# MCU.net
KiCad netlist of a schematic drawn in Altium Designer
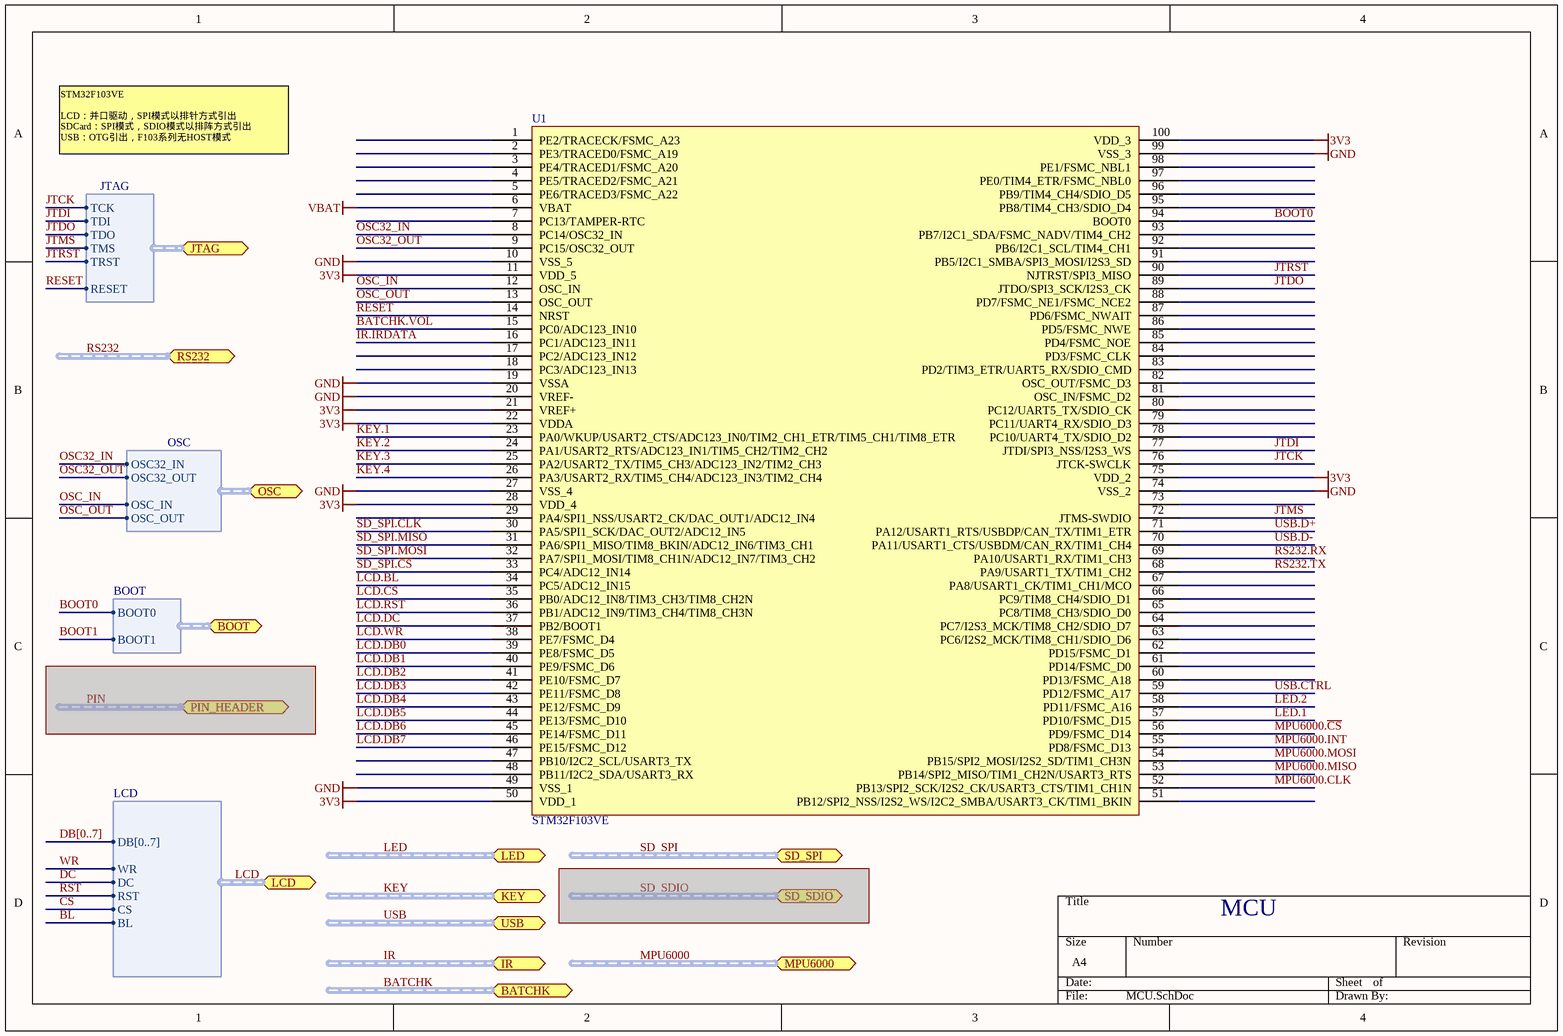
[diagram p0: MCU.SchDoc]

(export (version "E")
  (design (tool "Eeschema 10.0.6"))
  (components
    (comp (ref "U1")
      (value "STM32F103VE")
      (footprint "LQFP100_M")
      (libsource (lib "STM32F103VE") (part "STM32F103VE"))
    )
  )
  (nets
    (net (code "15") (name "/BATCHK.VOL") (class "Default")
      (node (ref "U1") (pin "15") (pinfunction "PC0/ADC123_IN10_15") (pintype "passive"))
    )
    (net (code "17") (name "/BOOT0") (class "Default")
      (node (ref "U1") (pin "94") (pinfunction "BOOT0_94") (pintype "passive"))
    )
    (net (code "21") (name "/IR.IRDATA") (class "Default")
      (node (ref "U1") (pin "16") (pinfunction "PC1/ADC123_IN11_16") (pintype "passive"))
    )
    (net (code "22") (name "/JTCK") (class "Default")
      (node (ref "U1") (pin "76") (pinfunction "JTCK-SWCLK_76") (pintype "passive"))
    )
    (net (code "23") (name "/JTDI") (class "Default")
      (node (ref "U1") (pin "77") (pinfunction "JTDI/SPI3_NSS/I2S3_WS_77") (pintype "passive"))
    )
    (net (code "24") (name "/JTDO") (class "Default")
      (node (ref "U1") (pin "89") (pinfunction "JTDO/SPI3_SCK/I2S3_CK_89") (pintype "passive"))
    )
    (net (code "25") (name "/JTMS") (class "Default")
      (node (ref "U1") (pin "72") (pinfunction "JTMS-SWDIO_72") (pintype "passive"))
    )
    (net (code "26") (name "/JTRST") (class "Default")
      (node (ref "U1") (pin "90") (pinfunction "NJTRST/SPI3_MISO_90") (pintype "passive"))
    )
    (net (code "27") (name "/KEY.1") (class "Default")
      (node (ref "U1") (pin "23") (pinfunction "PA0/WKUP/USART2_CTS/ADC123_IN0/TIM2_CH1_ETR/TIM5_CH1/TIM8_ETR_23") (pintype "passive"))
    )
    (net (code "28") (name "/KEY.2") (class "Default")
      (node (ref "U1") (pin "24") (pinfunction "PA1/USART2_RTS/ADC123_IN1/TIM5_CH2/TIM2_CH2_24") (pintype "passive"))
    )
    (net (code "29") (name "/KEY.3") (class "Default")
      (node (ref "U1") (pin "25") (pinfunction "PA2/USART2_TX/TIM5_CH3/ADC123_IN2/TIM2_CH3_25") (pintype "passive"))
    )
    (net (code "30") (name "/KEY.4") (class "Default")
      (node (ref "U1") (pin "26") (pinfunction "PA3/USART2_RX/TIM5_CH4/ADC123_IN3/TIM2_CH4_26") (pintype "passive"))
    )
    (net (code "31") (name "/LCD.BL") (class "Default")
      (node (ref "U1") (pin "34") (pinfunction "PC5/ADC12_IN15_34") (pintype "passive"))
    )
    (net (code "32") (name "/LCD.CS") (class "Default")
      (node (ref "U1") (pin "35") (pinfunction "PB0/ADC12_IN8/TIM3_CH3/TIM8_CH2N_35") (pintype "passive"))
    )
    (net (code "33") (name "/LCD.DB0") (class "Default")
      (node (ref "U1") (pin "39") (pinfunction "PE8/FSMC_D5_39") (pintype "passive"))
    )
    (net (code "34") (name "/LCD.DB1") (class "Default")
      (node (ref "U1") (pin "40") (pinfunction "PE9/FSMC_D6_40") (pintype "passive"))
    )
    (net (code "35") (name "/LCD.DB2") (class "Default")
      (node (ref "U1") (pin "41") (pinfunction "PE10/FSMC_D7_41") (pintype "passive"))
    )
    (net (code "36") (name "/LCD.DB3") (class "Default")
      (node (ref "U1") (pin "42") (pinfunction "PE11/FSMC_D8_42") (pintype "passive"))
    )
    (net (code "37") (name "/LCD.DB4") (class "Default")
      (node (ref "U1") (pin "43") (pinfunction "PE12/FSMC_D9_43") (pintype "passive"))
    )
    (net (code "38") (name "/LCD.DB5") (class "Default")
      (node (ref "U1") (pin "44") (pinfunction "PE13/FSMC_D10_44") (pintype "passive"))
    )
    (net (code "39") (name "/LCD.DB6") (class "Default")
      (node (ref "U1") (pin "45") (pinfunction "PE14/FSMC_D11_45") (pintype "passive"))
    )
    (net (code "40") (name "/LCD.DB7") (class "Default")
      (node (ref "U1") (pin "46") (pinfunction "PE15/FSMC_D12_46") (pintype "passive"))
    )
    (net (code "41") (name "/LCD.DC") (class "Default")
      (node (ref "U1") (pin "37") (pinfunction "PB2/BOOT1_37") (pintype "passive"))
    )
    (net (code "42") (name "/LCD.RST") (class "Default")
      (node (ref "U1") (pin "36") (pinfunction "PB1/ADC12_IN9/TIM3_CH4/TIM8_CH3N_36") (pintype "passive"))
    )
    (net (code "43") (name "/LCD.WR") (class "Default")
      (node (ref "U1") (pin "38") (pinfunction "PE7/FSMC_D4_38") (pintype "passive"))
    )
    (net (code "44") (name "/LED.1") (class "Default")
      (node (ref "U1") (pin "57") (pinfunction "PD10/FSMC_D15_57") (pintype "passive"))
    )
    (net (code "45") (name "/LED.2") (class "Default")
      (node (ref "U1") (pin "58") (pinfunction "PD11/FSMC_A16_58") (pintype "passive"))
    )
    (net (code "46") (name "/MPU6000.CLK") (class "Default")
      (node (ref "U1") (pin "52") (pinfunction "PB13/SPI2_SCK/I2S2_CK/USART3_CTS/TIM1_CH1N_52") (pintype "passive"))
    )
    (net (code "47") (name "/MPU6000.INT") (class "Default")
      (node (ref "U1") (pin "55") (pinfunction "PD8/FSMC_D13_55") (pintype "passive"))
    )
    (net (code "48") (name "/MPU6000.MISO") (class "Default")
      (node (ref "U1") (pin "53") (pinfunction "PB14/SPI2_MISO/TIM1_CH2N/USART3_RTS_53") (pintype "passive"))
    )
    (net (code "49") (name "/MPU6000.MOSI") (class "Default")
      (node (ref "U1") (pin "54") (pinfunction "PB15/SPI2_MOSI/I2S2_SD/TIM1_CH3N_54") (pintype "passive"))
    )
    (net (code "50") (name "/MPU6000.~{CS}") (class "Default")
      (node (ref "U1") (pin "56") (pinfunction "PD9/FSMC_D14_56") (pintype "passive"))
    )
    (net (code "51") (name "/OSC32_IN") (class "Default")
      (node (ref "U1") (pin "8") (pinfunction "PC14/OSC32_IN_8") (pintype "passive"))
    )
    (net (code "52") (name "/OSC32_OUT") (class "Default")
      (node (ref "U1") (pin "9") (pinfunction "PC15/OSC32_OUT_9") (pintype "passive"))
    )
    (net (code "53") (name "/OSC_IN") (class "Default")
      (node (ref "U1") (pin "12") (pinfunction "OSC_IN_12") (pintype "passive"))
    )
    (net (code "54") (name "/OSC_OUT") (class "Default")
      (node (ref "U1") (pin "13") (pinfunction "OSC_OUT_13") (pintype "passive"))
    )
    (net (code "55") (name "/RESET") (class "Default")
      (node (ref "U1") (pin "14") (pinfunction "NRST_14") (pintype "passive"))
    )
    (net (code "56") (name "/RS232.RX") (class "Default")
      (node (ref "U1") (pin "69") (pinfunction "PA10/USART1_RX/TIM1_CH3_69") (pintype "passive"))
    )
    (net (code "57") (name "/RS232.TX") (class "Default")
      (node (ref "U1") (pin "68") (pinfunction "PA9/USART1_TX/TIM1_CH2_68") (pintype "passive"))
    )
    (net (code "59") (name "/SD_SPI.CLK") (class "Default")
      (node (ref "U1") (pin "30") (pinfunction "PA5/SPI1_SCK/DAC_OUT2/ADC12_IN5_30") (pintype "passive"))
    )
    (net (code "60") (name "/SD_SPI.MISO") (class "Default")
      (node (ref "U1") (pin "31") (pinfunction "PA6/SPI1_MISO/TIM8_BKIN/ADC12_IN6/TIM3_CH1_31") (pintype "passive"))
    )
    (net (code "61") (name "/SD_SPI.MOSI") (class "Default")
      (node (ref "U1") (pin "32") (pinfunction "PA7/SPI1_MOSI/TIM8_CH1N/ADC12_IN7/TIM3_CH2_32") (pintype "passive"))
    )
    (net (code "62") (name "/SD_SPI.~{CS}") (class "Default")
      (node (ref "U1") (pin "33") (pinfunction "PC4/ADC12_IN14_33") (pintype "passive"))
    )
    (net (code "63") (name "/USB.CTRL") (class "Default")
      (node (ref "U1") (pin "59") (pinfunction "PD12/FSMC_A17_59") (pintype "passive"))
    )
    (net (code "64") (name "/USB.D+") (class "Default")
      (node (ref "U1") (pin "71") (pinfunction "PA12/USART1_RTS/USBDP/CAN_TX/TIM1_ETR_71") (pintype "passive"))
    )
    (net (code "65") (name "/USB.D-") (class "Default")
      (node (ref "U1") (pin "70") (pinfunction "PA11/USART1_CTS/USBDM/CAN_RX/TIM1_CH4_70") (pintype "passive"))
    )
    (net (code "82") (name "3V3") (class "Default")
      (node (ref "U1") (pin "100") (pinfunction "VDD_3_100") (pintype "passive"))
      (node (ref "U1") (pin "11") (pinfunction "VDD_5_11") (pintype "passive"))
      (node (ref "U1") (pin "21") (pinfunction "VREF+_21") (pintype "passive"))
      (node (ref "U1") (pin "22") (pinfunction "VDDA_22") (pintype "passive"))
      (node (ref "U1") (pin "28") (pinfunction "VDD_4_28") (pintype "passive"))
      (node (ref "U1") (pin "50") (pinfunction "VDD_1_50") (pintype "passive"))
      (node (ref "U1") (pin "75") (pinfunction "VDD_2_75") (pintype "passive"))
    )
    (net (code "83") (name "GND") (class "Default")
      (node (ref "U1") (pin "10") (pinfunction "VSS_5_10") (pintype "passive"))
      (node (ref "U1") (pin "19") (pinfunction "VSSA_19") (pintype "passive"))
      (node (ref "U1") (pin "20") (pinfunction "VREF-_20") (pintype "passive"))
      (node (ref "U1") (pin "27") (pinfunction "VSS_4_27") (pintype "passive"))
      (node (ref "U1") (pin "49") (pinfunction "VSS_1_49") (pintype "passive"))
      (node (ref "U1") (pin "74") (pinfunction "VSS_2_74") (pintype "passive"))
      (node (ref "U1") (pin "99") (pinfunction "VSS_3_99") (pintype "passive"))
    )
    (net (code "84") (name "VBAT") (class "Default")
      (node (ref "U1") (pin "6") (pinfunction "VBAT_6") (pintype "passive"))
    )
    (net (code "85") (name "unconnected-(U1-OSC_IN{slash}FSMC_D2-Pad81)") (class "Default")
      (node (ref "U1") (pin "81") (pinfunction "OSC_IN/FSMC_D2_81") (pintype "passive"))
    )
    (net (code "86") (name "unconnected-(U1-OSC_OUT{slash}FSMC_D3-Pad82)") (class "Default")
      (node (ref "U1") (pin "82") (pinfunction "OSC_OUT/FSMC_D3_82") (pintype "passive"))
    )
    (net (code "87") (name "unconnected-(U1-PA4{slash}SPI1_NSS{slash}USART2_CK{slash}DAC_OUT1{slash}ADC12_IN4-Pad29)") (class "Default")
      (node (ref "U1") (pin "29") (pinfunction "PA4/SPI1_NSS/USART2_CK/DAC_OUT1/ADC12_IN4_29") (pintype "passive"))
    )
    (net (code "88") (name "unconnected-(U1-PA8{slash}USART1_CK{slash}TIM1_CH1{slash}MCO-Pad67)") (class "Default")
      (node (ref "U1") (pin "67") (pinfunction "PA8/USART1_CK/TIM1_CH1/MCO_67") (pintype "passive"))
    )
    (net (code "89") (name "unconnected-(U1-PB5{slash}I2C1_SMBA{slash}SPI3_MOSI{slash}I2S3_SD-Pad91)") (class "Default")
      (node (ref "U1") (pin "91") (pinfunction "PB5/I2C1_SMBA/SPI3_MOSI/I2S3_SD_91") (pintype "passive"))
    )
    (net (code "90") (name "unconnected-(U1-PB6{slash}I2C1_SCL{slash}TIM4_CH1-Pad92)") (class "Default")
      (node (ref "U1") (pin "92") (pinfunction "PB6/I2C1_SCL/TIM4_CH1_92") (pintype "passive"))
    )
    (net (code "91") (name "unconnected-(U1-PB7{slash}I2C1_SDA{slash}FSMC_NADV{slash}TIM4_CH2-Pad93)") (class "Default")
      (node (ref "U1") (pin "93") (pinfunction "PB7/I2C1_SDA/FSMC_NADV/TIM4_CH2_93") (pintype "passive"))
    )
    (net (code "92") (name "unconnected-(U1-PB8{slash}TIM4_CH3{slash}SDIO_D4-Pad95)") (class "Default")
      (node (ref "U1") (pin "95") (pinfunction "PB8/TIM4_CH3/SDIO_D4_95") (pintype "passive"))
    )
    (net (code "93") (name "unconnected-(U1-PB9{slash}TIM4_CH4{slash}SDIO_D5-Pad96)") (class "Default")
      (node (ref "U1") (pin "96") (pinfunction "PB9/TIM4_CH4/SDIO_D5_96") (pintype "passive"))
    )
    (net (code "94") (name "unconnected-(U1-PB10{slash}I2C2_SCL{slash}USART3_TX-Pad47)") (class "Default")
      (node (ref "U1") (pin "47") (pinfunction "PB10/I2C2_SCL/USART3_TX_47") (pintype "passive"))
    )
    (net (code "95") (name "unconnected-(U1-PB11{slash}I2C2_SDA{slash}USART3_RX-Pad48)") (class "Default")
      (node (ref "U1") (pin "48") (pinfunction "PB11/I2C2_SDA/USART3_RX_48") (pintype "passive"))
    )
    (net (code "96") (name "unconnected-(U1-PB12{slash}SPI2_NSS{slash}I2S2_WS{slash}I2C2_SMBA{slash}USART3_CK{slash}TIM1_BKIN-Pad51)") (class "Default")
      (node (ref "U1") (pin "51") (pinfunction "PB12/SPI2_NSS/I2S2_WS/I2C2_SMBA/USART3_CK/TIM1_BKIN_51") (pintype "passive"))
    )
    (net (code "97") (name "unconnected-(U1-PC2{slash}ADC123_IN12-Pad17)") (class "Default")
      (node (ref "U1") (pin "17") (pinfunction "PC2/ADC123_IN12_17") (pintype "passive"))
    )
    (net (code "98") (name "unconnected-(U1-PC3{slash}ADC123_IN13-Pad18)") (class "Default")
      (node (ref "U1") (pin "18") (pinfunction "PC3/ADC123_IN13_18") (pintype "passive"))
    )
    (net (code "99") (name "unconnected-(U1-PC6{slash}I2S2_MCK{slash}TIM8_CH1{slash}SDIO_D6-Pad63)") (class "Default")
      (node (ref "U1") (pin "63") (pinfunction "PC6/I2S2_MCK/TIM8_CH1/SDIO_D6_63") (pintype "passive"))
    )
    (net (code "100") (name "unconnected-(U1-PC7{slash}I2S3_MCK{slash}TIM8_CH2{slash}SDIO_D7-Pad64)") (class "Default")
      (node (ref "U1") (pin "64") (pinfunction "PC7/I2S3_MCK/TIM8_CH2/SDIO_D7_64") (pintype "passive"))
    )
    (net (code "101") (name "unconnected-(U1-PC8{slash}TIM8_CH3{slash}SDIO_D0-Pad65)") (class "Default")
      (node (ref "U1") (pin "65") (pinfunction "PC8/TIM8_CH3/SDIO_D0_65") (pintype "passive"))
    )
    (net (code "102") (name "unconnected-(U1-PC9{slash}TIM8_CH4{slash}SDIO_D1-Pad66)") (class "Default")
      (node (ref "U1") (pin "66") (pinfunction "PC9/TIM8_CH4/SDIO_D1_66") (pintype "passive"))
    )
    (net (code "103") (name "unconnected-(U1-PC10{slash}UART4_TX{slash}SDIO_D2-Pad78)") (class "Default")
      (node (ref "U1") (pin "78") (pinfunction "PC10/UART4_TX/SDIO_D2_78") (pintype "passive"))
    )
    (net (code "104") (name "unconnected-(U1-PC11{slash}UART4_RX{slash}SDIO_D3-Pad79)") (class "Default")
      (node (ref "U1") (pin "79") (pinfunction "PC11/UART4_RX/SDIO_D3_79") (pintype "passive"))
    )
    (net (code "105") (name "unconnected-(U1-PC12{slash}UART5_TX{slash}SDIO_CK-Pad80)") (class "Default")
      (node (ref "U1") (pin "80") (pinfunction "PC12/UART5_TX/SDIO_CK_80") (pintype "passive"))
    )
    (net (code "106") (name "unconnected-(U1-PC13{slash}TAMPER-RTC-Pad7)") (class "Default")
      (node (ref "U1") (pin "7") (pinfunction "PC13/TAMPER-RTC_7") (pintype "passive"))
    )
    (net (code "107") (name "unconnected-(U1-PD2{slash}TIM3_ETR{slash}UART5_RX{slash}SDIO_CMD-Pad83)") (class "Default")
      (node (ref "U1") (pin "83") (pinfunction "PD2/TIM3_ETR/UART5_RX/SDIO_CMD_83") (pintype "passive"))
    )
    (net (code "108") (name "unconnected-(U1-PD3{slash}FSMC_CLK-Pad84)") (class "Default")
      (node (ref "U1") (pin "84") (pinfunction "PD3/FSMC_CLK_84") (pintype "passive"))
    )
    (net (code "109") (name "unconnected-(U1-PD4{slash}FSMC_NOE-Pad85)") (class "Default")
      (node (ref "U1") (pin "85") (pinfunction "PD4/FSMC_NOE_85") (pintype "passive"))
    )
    (net (code "110") (name "unconnected-(U1-PD5{slash}FSMC_NWE-Pad86)") (class "Default")
      (node (ref "U1") (pin "86") (pinfunction "PD5/FSMC_NWE_86") (pintype "passive"))
    )
    (net (code "111") (name "unconnected-(U1-PD6{slash}FSMC_NWAIT-Pad87)") (class "Default")
      (node (ref "U1") (pin "87") (pinfunction "PD6/FSMC_NWAIT_87") (pintype "passive"))
    )
    (net (code "112") (name "unconnected-(U1-PD7{slash}FSMC_NE1{slash}FSMC_NCE2-Pad88)") (class "Default")
      (node (ref "U1") (pin "88") (pinfunction "PD7/FSMC_NE1/FSMC_NCE2_88") (pintype "passive"))
    )
    (net (code "113") (name "unconnected-(U1-PD13{slash}FSMC_A18-Pad60)") (class "Default")
      (node (ref "U1") (pin "60") (pinfunction "PD13/FSMC_A18_60") (pintype "passive"))
    )
    (net (code "114") (name "unconnected-(U1-PD14{slash}FSMC_D0-Pad61)") (class "Default")
      (node (ref "U1") (pin "61") (pinfunction "PD14/FSMC_D0_61") (pintype "passive"))
    )
    (net (code "115") (name "unconnected-(U1-PD15{slash}FSMC_D1-Pad62)") (class "Default")
      (node (ref "U1") (pin "62") (pinfunction "PD15/FSMC_D1_62") (pintype "passive"))
    )
    (net (code "116") (name "unconnected-(U1-PE0{slash}TIM4_ETR{slash}FSMC_NBL0-Pad97)") (class "Default")
      (node (ref "U1") (pin "97") (pinfunction "PE0/TIM4_ETR/FSMC_NBL0_97") (pintype "passive"))
    )
    (net (code "117") (name "unconnected-(U1-PE1{slash}FSMC_NBL1-Pad98)") (class "Default")
      (node (ref "U1") (pin "98") (pinfunction "PE1/FSMC_NBL1_98") (pintype "passive"))
    )
    (net (code "118") (name "unconnected-(U1-PE2{slash}TRACECK{slash}FSMC_A23-Pad1)") (class "Default")
      (node (ref "U1") (pin "1") (pinfunction "PE2/TRACECK/FSMC_A23_1") (pintype "passive"))
    )
    (net (code "119") (name "unconnected-(U1-PE3{slash}TRACED0{slash}FSMC_A19-Pad2)") (class "Default")
      (node (ref "U1") (pin "2") (pinfunction "PE3/TRACED0/FSMC_A19_2") (pintype "passive"))
    )
    (net (code "120") (name "unconnected-(U1-PE4{slash}TRACED1{slash}FSMC_A20-Pad3)") (class "Default")
      (node (ref "U1") (pin "3") (pinfunction "PE4/TRACED1/FSMC_A20_3") (pintype "passive"))
    )
    (net (code "121") (name "unconnected-(U1-PE5{slash}TRACED2{slash}FSMC_A21-Pad4)") (class "Default")
      (node (ref "U1") (pin "4") (pinfunction "PE5/TRACED2/FSMC_A21_4") (pintype "passive"))
    )
    (net (code "122") (name "unconnected-(U1-PE6{slash}TRACED3{slash}FSMC_A22-Pad5)") (class "Default")
      (node (ref "U1") (pin "5") (pinfunction "PE6/TRACED3/FSMC_A22_5") (pintype "passive"))
    )
    (net (code "123") (name "unconnected-(U1-Pad73)") (class "Default")
      (node (ref "U1") (pin "73") (pintype "passive"))
    )
  )
)
